# PL-N823-01_Breakout.net
KiCad netlist of a schematic drawn in EAGLE
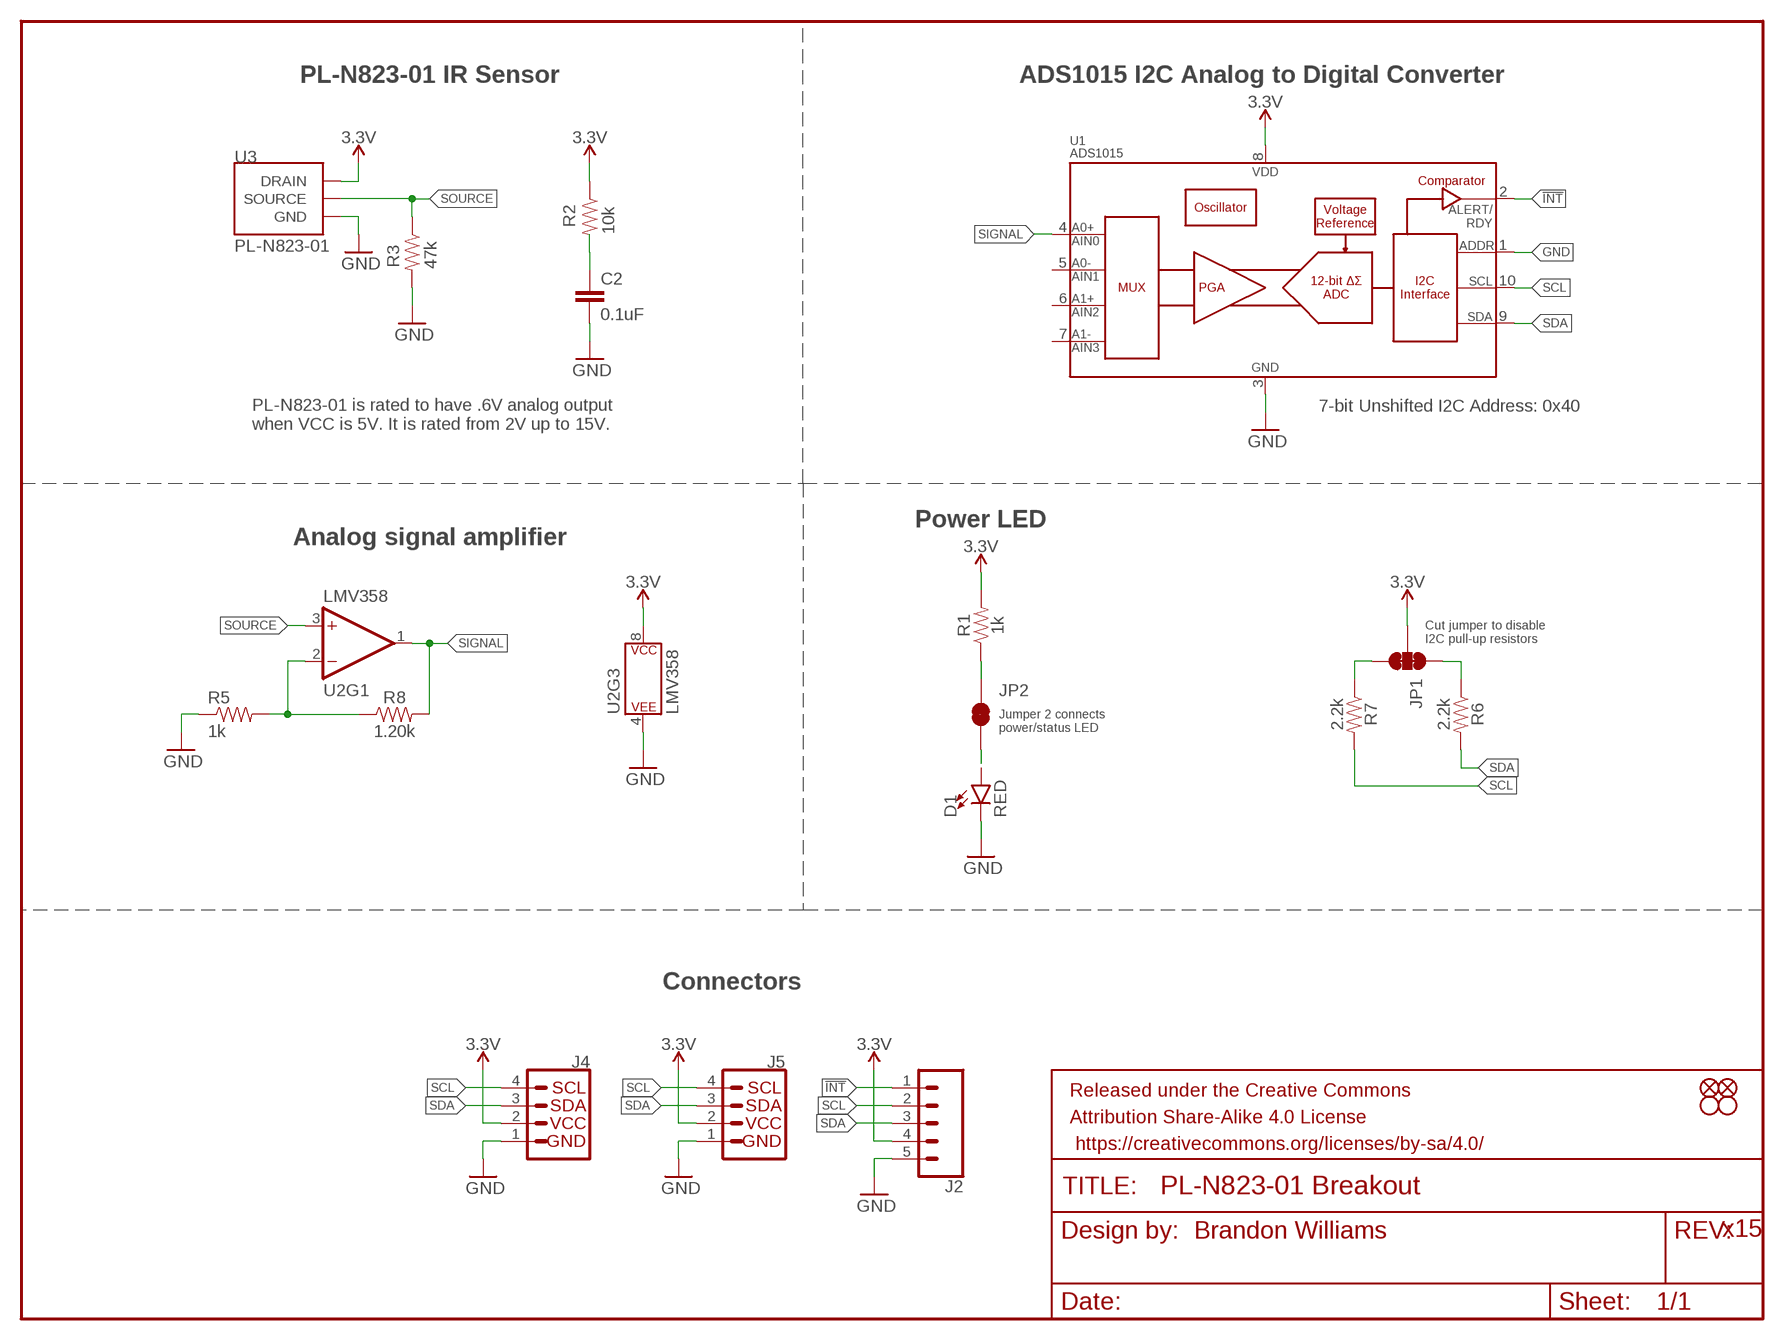
[diagram p0: schematic, sheet 1]

(export (version "E")
  (design (tool "Eeschema 10.0.6"))
  (components
    (comp (ref "C2")
      (value "0.1uF")
      (footprint "eagle-import:0603")
      (libsource (lib "eagle-import") (part "0.1UF-0603-25V-(+80/-20%)"))
    )
    (comp (ref "D1")
      (value "RED")
      (footprint "eagle-import:LED-0603")
      (libsource (lib "eagle-import") (part "LED-RED0603"))
    )
    (comp (ref "FD1")
      (value "FIDUCIALUFIDUCIAL")
      (footprint "eagle-import:FIDUCIAL-MICRO")
      (libsource (lib "eagle-import") (part "FIDUCIALUFIDUCIAL"))
    )
    (comp (ref "FD2")
      (value "FIDUCIALUFIDUCIAL")
      (footprint "eagle-import:FIDUCIAL-MICRO")
      (libsource (lib "eagle-import") (part "FIDUCIALUFIDUCIAL"))
    )
    (comp (ref "FRAME1")
      (value "FRAME-LETTERNO_PACKAGE")
      (footprint "eagle-import:DUMMY")
      (fields (field (name "DESIGNER") "Nobody"))
      (libsource (lib "eagle-import") (part "FRAME-LETTERNO_PACKAGE"))
    )
    (comp (ref "H1")
      (value "STAND-OFFTIGHT")
      (footprint "eagle-import:STAND-OFF-TIGHT")
      (libsource (lib "eagle-import") (part "STAND-OFFTIGHT"))
    )
    (comp (ref "H2")
      (value "STAND-OFFTIGHT")
      (footprint "eagle-import:STAND-OFF-TIGHT")
      (libsource (lib "eagle-import") (part "STAND-OFFTIGHT"))
    )
    (comp (ref "J2")
      (value "CONN_05NO_SILK")
      (footprint "eagle-import:1X05_NO_SILK")
      (libsource (lib "eagle-import") (part "CONN_05NO_SILK"))
    )
    (comp (ref "J4")
      (value "QWIIC_CONNECTORJS-1MM")
      (footprint "eagle-import:JST04_1MM_RA")
      (libsource (lib "eagle-import") (part "QWIIC_CONNECTORJS-1MM"))
    )
    (comp (ref "J5")
      (value "QWIIC_CONNECTORJS-1MM")
      (footprint "eagle-import:JST04_1MM_RA")
      (libsource (lib "eagle-import") (part "QWIIC_CONNECTORJS-1MM"))
    )
    (comp (ref "JP1")
      (value "JUMPER-SMT_3_2-NC_TRACE_SILK")
      (footprint "eagle-import:SMT-JUMPER_3_2-NC_TRACE_SILK")
      (libsource (lib "eagle-import") (part "JUMPER-SMT_3_2-NC_TRACE_SILK"))
    )
    (comp (ref "JP2")
      (value "JUMPER-SMT_2_NC_TRACE_SILK")
      (footprint "eagle-import:SMT-JUMPER_2_NC_TRACE_SILK")
      (libsource (lib "eagle-import") (part "JUMPER-SMT_2_NC_TRACE_SILK"))
    )
    (comp (ref "R1")
      (value "1k")
      (footprint "eagle-import:0603")
      (libsource (lib "eagle-import") (part "1KOHM-0603-1/10W-1%"))
    )
    (comp (ref "R2")
      (value "10k")
      (footprint "eagle-import:0603")
      (libsource (lib "eagle-import") (part "10KOHM-0603-1/10W-1%"))
    )
    (comp (ref "R3")
      (value "47k")
      (footprint "eagle-import:0603")
      (libsource (lib "eagle-import") (part "47KOHM-0603-1/10W-1%"))
    )
    (comp (ref "R5")
      (value "1k")
      (footprint "eagle-import:0603")
      (libsource (lib "eagle-import") (part "1KOHM-0603-1/10W-1%"))
    )
    (comp (ref "R6")
      (value "2.2k")
      (footprint "eagle-import:0603")
      (libsource (lib "eagle-import") (part "2.2KOHM-0603-1/10W-1%"))
    )
    (comp (ref "R7")
      (value "2.2k")
      (footprint "eagle-import:0603")
      (libsource (lib "eagle-import") (part "2.2KOHM-0603-1/10W-1%"))
    )
    (comp (ref "R8")
      (value "1.20k")
      (footprint "eagle-import:0603")
      (libsource (lib "eagle-import") (part "1.20KOHM-0603-1/10W-1%"))
    )
    (comp (ref "U1")
      (value "ADS1015")
      (footprint "eagle-import:MSOP10")
      (libsource (lib "eagle-import") (part "ADS1015"))
    )
    (comp (ref "U2")
      (value "LMV358")
      (footprint "eagle-import:SO08")
      (libsource (lib "eagle-import") (part "LMV358SOIC"))
    )
    (comp (ref "U3")
      (value "PL-N823-01")
      (footprint "eagle-import:PL-N823-01")
      (libsource (lib "eagle-import") (part "PL-N823-01"))
    )
  )
  (nets
    (net (code "1") (name "/~{INT}") (class "Default")
      (node (ref "J2") (pin "1") (pinfunction "1_1") (pintype "passive"))
      (node (ref "U1") (pin "2") (pinfunction "ALERT/RDY_2") (pintype "bidirectional"))
    )
    (net (code "2") (name "3.3V") (class "Default")
      (node (ref "J2") (pin "4") (pinfunction "4_4") (pintype "passive"))
      (node (ref "J4") (pin "2") (pinfunction "2_2") (pintype "power_in"))
      (node (ref "J5") (pin "2") (pinfunction "2_2") (pintype "power_in"))
      (node (ref "JP1") (pin "2") (pinfunction "2_2") (pintype "passive"))
      (node (ref "R1") (pin "2") (pinfunction "2_2") (pintype "passive"))
      (node (ref "R2") (pin "1") (pinfunction "1_1") (pintype "passive"))
      (node (ref "U1") (pin "8") (pinfunction "VDD_8") (pintype "bidirectional"))
      (node (ref "U2") (pin "8") (pinfunction "P$V+_8") (pintype "bidirectional"))
      (node (ref "U3") (pin "DRAIN") (pinfunction "DRAIN_DRAIN") (pintype "input"))
    )
    (net (code "3") (name "GND") (class "Default")
      (node (ref "C2") (pin "2") (pinfunction "2_2") (pintype "passive"))
      (node (ref "D1") (pin "C") (pinfunction "C_C") (pintype "passive"))
      (node (ref "J2") (pin "5") (pinfunction "5_5") (pintype "passive"))
      (node (ref "J4") (pin "1") (pinfunction "1_1") (pintype "power_in"))
      (node (ref "J5") (pin "1") (pinfunction "1_1") (pintype "power_in"))
      (node (ref "R3") (pin "2") (pinfunction "2_2") (pintype "passive"))
      (node (ref "R5") (pin "1") (pinfunction "1_1") (pintype "passive"))
      (node (ref "U1") (pin "1") (pinfunction "ADDR_1") (pintype "bidirectional"))
      (node (ref "U1") (pin "3") (pinfunction "VSS_3") (pintype "bidirectional"))
      (node (ref "U2") (pin "4") (pinfunction "P$V-_4") (pintype "bidirectional"))
      (node (ref "U3") (pin "GND@1") (pinfunction "GND_GND@1") (pintype "power_in"))
      (node (ref "U3") (pin "GND@2") (pinfunction "GND_GND@2") (pintype "power_in"))
    )
    (net (code "4") (name "Net-(C2-Pad1)") (class "Default")
      (node (ref "C2") (pin "1") (pinfunction "1_1") (pintype "passive"))
      (node (ref "R2") (pin "2") (pinfunction "2_2") (pintype "passive"))
    )
    (net (code "5") (name "Net-(D1-PadA)") (class "Default")
      (node (ref "D1") (pin "A") (pinfunction "A_A") (pintype "passive"))
      (node (ref "JP2") (pin "2") (pinfunction "2_2") (pintype "passive"))
    )
    (net (code "6") (name "Net-(JP1-Pad1)") (class "Default")
      (node (ref "JP1") (pin "1") (pinfunction "1_1") (pintype "passive"))
      (node (ref "R6") (pin "1") (pinfunction "1_1") (pintype "passive"))
    )
    (net (code "7") (name "Net-(JP1-Pad3)") (class "Default")
      (node (ref "JP1") (pin "3") (pinfunction "3_3") (pintype "passive"))
      (node (ref "R7") (pin "1") (pinfunction "1_1") (pintype "passive"))
    )
    (net (code "8") (name "Net-(JP2-Pad1)") (class "Default")
      (node (ref "JP2") (pin "1") (pinfunction "1_1") (pintype "passive"))
      (node (ref "R1") (pin "1") (pinfunction "1_1") (pintype "passive"))
    )
    (net (code "9") (name "Net-(U2A--IN)") (class "Default")
      (node (ref "R5") (pin "2") (pinfunction "2_2") (pintype "passive"))
      (node (ref "R8") (pin "1") (pinfunction "1_1") (pintype "passive"))
      (node (ref "U2") (pin "2") (pinfunction "-IN_2") (pintype "input"))
    )
    (net (code "10") (name "SCL") (class "Default")
      (node (ref "J2") (pin "2") (pinfunction "2_2") (pintype "passive"))
      (node (ref "J4") (pin "4") (pinfunction "4_4") (pintype "passive"))
      (node (ref "J5") (pin "4") (pinfunction "4_4") (pintype "passive"))
      (node (ref "R7") (pin "2") (pinfunction "2_2") (pintype "passive"))
      (node (ref "U1") (pin "10") (pinfunction "SCL_10") (pintype "bidirectional"))
    )
    (net (code "11") (name "SDA") (class "Default")
      (node (ref "J2") (pin "3") (pinfunction "3_3") (pintype "passive"))
      (node (ref "J4") (pin "3") (pinfunction "3_3") (pintype "passive"))
      (node (ref "J5") (pin "3") (pinfunction "3_3") (pintype "passive"))
      (node (ref "R6") (pin "2") (pinfunction "2_2") (pintype "passive"))
      (node (ref "U1") (pin "9") (pinfunction "SDA_9") (pintype "bidirectional"))
    )
    (net (code "12") (name "SIGNAL") (class "Default")
      (node (ref "R8") (pin "2") (pinfunction "2_2") (pintype "passive"))
      (node (ref "U1") (pin "4") (pinfunction "AIN0_4") (pintype "bidirectional"))
      (node (ref "U2") (pin "1") (pinfunction "OUT_1") (pintype "output"))
    )
    (net (code "13") (name "SOURCE") (class "Default")
      (node (ref "R3") (pin "1") (pinfunction "1_1") (pintype "passive"))
      (node (ref "U2") (pin "3") (pinfunction "+IN_3") (pintype "input"))
      (node (ref "U3") (pin "SOURCE") (pinfunction "SOURCE_SOURCE") (pintype "output"))
    )
    (net (code "14") (name "unconnected-(U1-AIN1-Pad5)") (class "Default")
      (node (ref "U1") (pin "5") (pinfunction "AIN1_5") (pintype "bidirectional"))
    )
    (net (code "15") (name "unconnected-(U1-AIN2-Pad6)") (class "Default")
      (node (ref "U1") (pin "6") (pinfunction "AIN2_6") (pintype "bidirectional"))
    )
    (net (code "16") (name "unconnected-(U1-AIN3-Pad7)") (class "Default")
      (node (ref "U1") (pin "7") (pinfunction "AIN3_7") (pintype "bidirectional"))
    )
  )
)
